# MagnetorquerFinalBoard.net
KiCad netlist of a schematic drawn in Altium Designer
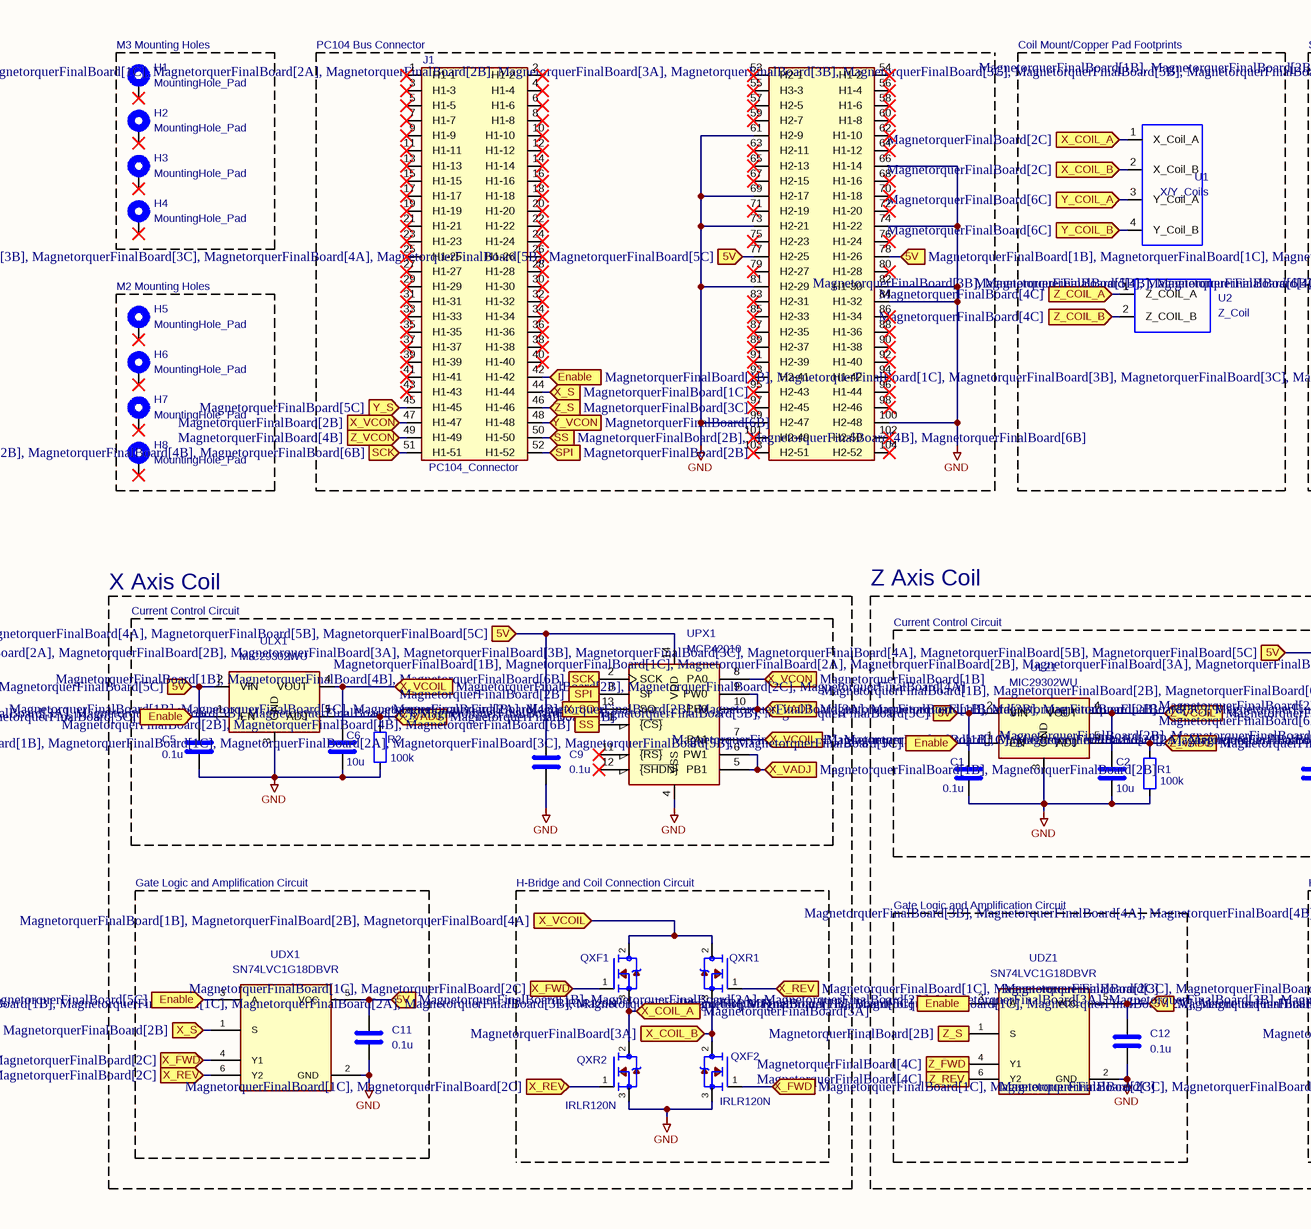
[diagram p0: MagnetorquerFinalBoard.SchDoc, left]
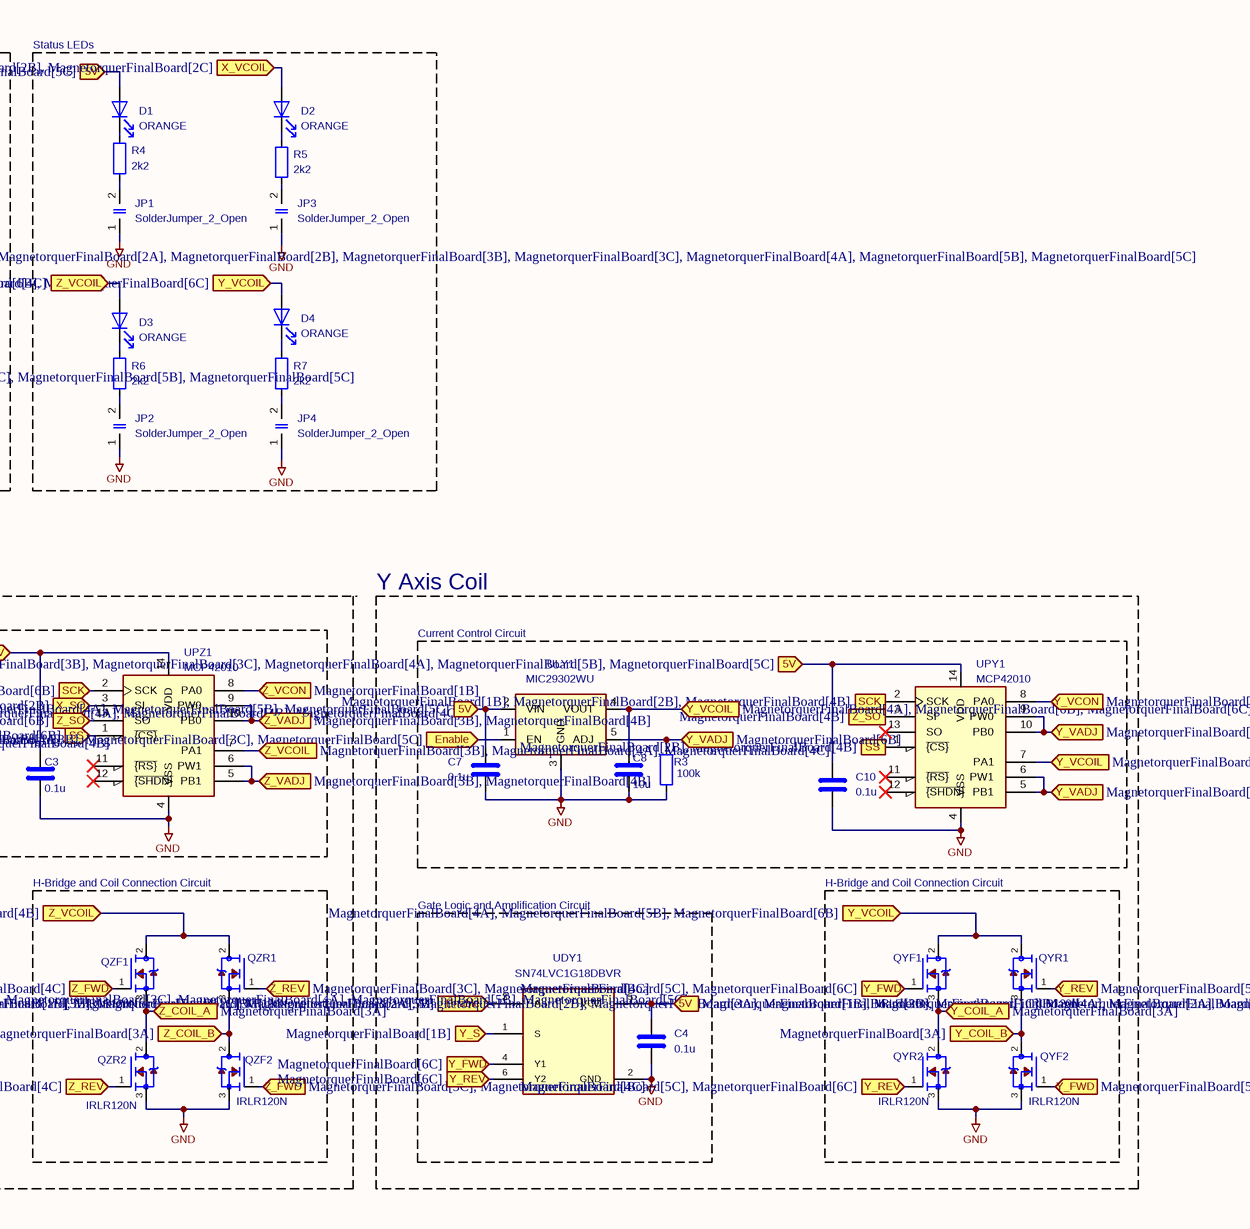
[diagram p1: MagnetorquerFinalBoard.SchDoc, right]

(export (version "E")
  (design (tool "Eeschema 10.0.6"))
  (components
    (comp (ref "C1") (value "0.1u") (footprint "C_0603_1608Metric") (libsource (lib "Device") (part "C")))
    (comp (ref "C2") (value "10u") (footprint "C_0603_1608Metric") (libsource (lib "Device") (part "C")))
    (comp (ref "C3") (value "0.1u") (footprint "C_0603_1608Metric") (libsource (lib "Device") (part "C")))
    (comp (ref "C4") (value "0.1u") (footprint "C_0603_1608Metric") (libsource (lib "Device") (part "C")))
    (comp (ref "C5") (value "0.1u") (footprint "C_0603_1608Metric") (libsource (lib "Device") (part "C")))
    (comp (ref "C6") (value "10u") (footprint "C_0603_1608Metric") (libsource (lib "Device") (part "C")))
    (comp (ref "C7") (value "0.1u") (footprint "C_0603_1608Metric") (libsource (lib "Device") (part "C")))
    (comp (ref "C8") (value "10u") (footprint "C_0603_1608Metric") (libsource (lib "Device") (part "C")))
    (comp (ref "C9") (value "0.1u") (footprint "C_0603_1608Metric") (libsource (lib "Device") (part "C")))
    (comp (ref "C10") (value "0.1u") (footprint "C_0603_1608Metric") (libsource (lib "Device") (part "C")))
    (comp (ref "C11") (value "0.1u") (footprint "C_0603_1608Metric") (libsource (lib "Device") (part "C")))
    (comp (ref "C12") (value "0.1u") (footprint "C_0603_1608Metric") (libsource (lib "Device") (part "C")))
    (comp (ref "D1")
      (value "ORANGE")
      (footprint "LED_0603_1608Metric")
      (libsource (lib "Device") (part "LED"))
    )
    (comp (ref "D2")
      (value "ORANGE")
      (footprint "LED_0603_1608Metric")
      (libsource (lib "Device") (part "LED"))
    )
    (comp (ref "D3")
      (value "ORANGE")
      (footprint "LED_0603_1608Metric")
      (libsource (lib "Device") (part "LED"))
    )
    (comp (ref "D4")
      (value "ORANGE")
      (footprint "LED_0603_1608Metric")
      (libsource (lib "Device") (part "LED"))
    )
    (comp (ref "H1")
      (value "MountingHole_Pad")
      (footprint "MountingHole_3.2mm_M3_Pad_TopBottom")
      (libsource (lib "Mechanical") (part "MountingHole_Pad"))
    )
    (comp (ref "H2")
      (value "MountingHole_Pad")
      (footprint "MountingHole_3.2mm_M3_Pad_TopBottom")
      (libsource (lib "Mechanical") (part "MountingHole_Pad"))
    )
    (comp (ref "H3")
      (value "MountingHole_Pad")
      (footprint "MountingHole_3.2mm_M3_Pad_TopBottom")
      (libsource (lib "Mechanical") (part "MountingHole_Pad"))
    )
    (comp (ref "H4")
      (value "MountingHole_Pad")
      (footprint "MountingHole_3.2mm_M3_Pad_TopBottom")
      (libsource (lib "Mechanical") (part "MountingHole_Pad"))
    )
    (comp (ref "H5")
      (value "MountingHole_Pad")
      (footprint "MountingHole_2.2mm_M2_Pad_TopBottom")
      (libsource (lib "Mechanical") (part "MountingHole_Pad"))
    )
    (comp (ref "H6")
      (value "MountingHole_Pad")
      (footprint "MountingHole_2.2mm_M2_Pad_TopBottom")
      (libsource (lib "Mechanical") (part "MountingHole_Pad"))
    )
    (comp (ref "H7")
      (value "MountingHole_Pad")
      (footprint "MountingHole_2.2mm_M2_Pad_TopBottom")
      (libsource (lib "Mechanical") (part "MountingHole_Pad"))
    )
    (comp (ref "H8")
      (value "MountingHole_Pad")
      (footprint "MountingHole_2.2mm_M2_Pad_TopBottom")
      (libsource (lib "Mechanical") (part "MountingHole_Pad"))
    )
    (comp (ref "J1")
      (value "PC104_Connector")
      (footprint "pc104-connector")
      (libsource (lib "qset-connector-library") (part "PC104_Connector"))
    )
    (comp (ref "JP1")
      (value "SolderJumper_2_Open")
      (footprint "SolderJumper-2_P1.3mm_Open_TrianglePad1.0x1.5mm")
      (libsource (lib "Jumper") (part "SolderJumper_2_Open"))
    )
    (comp (ref "JP2")
      (value "SolderJumper_2_Open")
      (footprint "SolderJumper-2_P1.3mm_Open_TrianglePad1.0x1.5mm")
      (libsource (lib "Jumper") (part "SolderJumper_2_Open"))
    )
    (comp (ref "JP3")
      (value "SolderJumper_2_Open")
      (footprint "SolderJumper-2_P1.3mm_Open_TrianglePad1.0x1.5mm")
      (libsource (lib "Jumper") (part "SolderJumper_2_Open"))
    )
    (comp (ref "JP4")
      (value "SolderJumper_2_Open")
      (footprint "SolderJumper-2_P1.3mm_Open_TrianglePad1.0x1.5mm")
      (libsource (lib "Jumper") (part "SolderJumper_2_Open"))
    )
    (comp (ref "QXF1")
      (value "IRLR120N")
      (footprint "TO-252-2")
      (fields (field (name "MANUFACTURER") "Infineon Technologies"))
      (libsource (lib "IRLR120N") (part "IRLR120N"))
    )
    (comp (ref "QXF2")
      (value "IRLR120N")
      (footprint "TO-252-2")
      (fields (field (name "MANUFACTURER") "Infineon Technologies"))
      (libsource (lib "IRLR120N") (part "IRLR120N"))
    )
    (comp (ref "QXR1")
      (value "IRLR120N")
      (footprint "TO-252-2")
      (fields (field (name "MANUFACTURER") "Infineon Technologies"))
      (libsource (lib "IRLR120N") (part "IRLR120N"))
    )
    (comp (ref "QXR2")
      (value "IRLR120N")
      (footprint "TO-252-2")
      (fields (field (name "MANUFACTURER") "Infineon Technologies"))
      (libsource (lib "IRLR120N") (part "IRLR120N"))
    )
    (comp (ref "QYF1")
      (value "IRLR120N")
      (footprint "TO-252-2")
      (fields (field (name "MANUFACTURER") "Infineon Technologies"))
      (libsource (lib "IRLR120N") (part "IRLR120N"))
    )
    (comp (ref "QYF2")
      (value "IRLR120N")
      (footprint "TO-252-2")
      (fields (field (name "MANUFACTURER") "Infineon Technologies"))
      (libsource (lib "IRLR120N") (part "IRLR120N"))
    )
    (comp (ref "QYR1")
      (value "IRLR120N")
      (footprint "TO-252-2")
      (fields (field (name "MANUFACTURER") "Infineon Technologies"))
      (libsource (lib "IRLR120N") (part "IRLR120N"))
    )
    (comp (ref "QYR2")
      (value "IRLR120N")
      (footprint "TO-252-2")
      (fields (field (name "MANUFACTURER") "Infineon Technologies"))
      (libsource (lib "IRLR120N") (part "IRLR120N"))
    )
    (comp (ref "QZF1")
      (value "IRLR120N")
      (footprint "TO-252-2")
      (fields (field (name "MANUFACTURER") "Infineon Technologies"))
      (libsource (lib "IRLR120N") (part "IRLR120N"))
    )
    (comp (ref "QZF2")
      (value "IRLR120N")
      (footprint "TO-252-2")
      (fields (field (name "MANUFACTURER") "Infineon Technologies"))
      (libsource (lib "IRLR120N") (part "IRLR120N"))
    )
    (comp (ref "QZR1")
      (value "IRLR120N")
      (footprint "TO-252-2")
      (fields (field (name "MANUFACTURER") "Infineon Technologies"))
      (libsource (lib "IRLR120N") (part "IRLR120N"))
    )
    (comp (ref "QZR2")
      (value "IRLR120N")
      (footprint "TO-252-2")
      (fields (field (name "MANUFACTURER") "Infineon Technologies"))
      (libsource (lib "IRLR120N") (part "IRLR120N"))
    )
    (comp (ref "R1") (value "100k") (footprint "R_0603_1608Metric") (libsource (lib "Device") (part "R")))
    (comp (ref "R2") (value "100k") (footprint "R_0603_1608Metric") (libsource (lib "Device") (part "R")))
    (comp (ref "R3") (value "100k") (footprint "R_0603_1608Metric") (libsource (lib "Device") (part "R")))
    (comp (ref "R4") (value "2k2") (footprint "R_0603_1608Metric") (libsource (lib "") (part "R_1")))
    (comp (ref "R5") (value "2k2") (footprint "R_0603_1608Metric") (libsource (lib "") (part "R_1")))
    (comp (ref "R6") (value "2k2") (footprint "R_0603_1608Metric") (libsource (lib "") (part "R_1")))
    (comp (ref "R7") (value "2k2") (footprint "R_0603_1608Metric") (libsource (lib "") (part "R_1")))
    (comp (ref "U1")
      (value "X/Y_Coils")
      (footprint "Front Coils Mount")
      (libsource (lib "Coils") (part "X/Y_Coils"))
    )
    (comp (ref "U2") (value "Z_Coil") (footprint "ZCoil") (libsource (lib "Coils") (part "Z_Coil")))
    (comp (ref "UDX1")
      (value "SN74LVC1G18DBVR")
      (footprint "SOT95P280X145-6N")
      (libsource (lib "SN74LVC1G18DBVR") (part "SN74LVC1G18DBVR"))
    )
    (comp (ref "UDY1")
      (value "SN74LVC1G18DBVR")
      (footprint "SOT95P280X145-6N")
      (libsource (lib "SN74LVC1G18DBVR") (part "SN74LVC1G18DBVR"))
    )
    (comp (ref "UDZ1")
      (value "SN74LVC1G18DBVR")
      (footprint "SOT95P280X145-6N")
      (libsource (lib "SN74LVC1G18DBVR") (part "SN74LVC1G18DBVR"))
    )
    (comp (ref "ULX1")
      (value "MIC29302WU")
      (footprint "TO-263-5_TabPin3")
      (libsource (lib "Regulator_Linear") (part "MIC29302WU"))
    )
    (comp (ref "ULY1")
      (value "MIC29302WU")
      (footprint "TO-263-5_TabPin3")
      (libsource (lib "Regulator_Linear") (part "MIC29302WU"))
    )
    (comp (ref "ULZ1")
      (value "MIC29302WU")
      (footprint "TO-263-5_TabPin3")
      (libsource (lib "Regulator_Linear") (part "MIC29302WU"))
    )
    (comp (ref "UPX1")
      (value "MCP42010")
      (footprint "SOIC127P600X175-14N")
      (libsource (lib "Potentiometer_Digital") (part "MCP42010"))
    )
    (comp (ref "UPY1")
      (value "MCP42010")
      (footprint "SOIC127P600X175-14N")
      (libsource (lib "Potentiometer_Digital") (part "MCP42010"))
    )
    (comp (ref "UPZ1")
      (value "MCP42010")
      (footprint "SOIC127P600X175-14N")
      (libsource (lib "Potentiometer_Digital") (part "MCP42010"))
    )
  )
  (nets
    (net (code "1") (name "/5V") (class "Default")
      (node (ref "C1") (pin "1") (pinfunction "1_1") (pintype "passive"))
      (node (ref "C10") (pin "1") (pinfunction "1_1") (pintype "passive"))
      (node (ref "C11") (pin "1") (pinfunction "1_1") (pintype "passive"))
      (node (ref "C12") (pin "1") (pinfunction "1_1") (pintype "passive"))
      (node (ref "C3") (pin "1") (pinfunction "1_1") (pintype "passive"))
      (node (ref "C4") (pin "1") (pinfunction "1_1") (pintype "passive"))
      (node (ref "C5") (pin "1") (pinfunction "1_1") (pintype "passive"))
      (node (ref "C7") (pin "1") (pinfunction "1_1") (pintype "passive"))
      (node (ref "C9") (pin "1") (pinfunction "1_1") (pintype "passive"))
      (node (ref "D1") (pin "2") (pinfunction "A_2") (pintype "passive"))
      (node (ref "J1") (pin "77") (pinfunction "H2-25_77") (pintype "passive"))
      (node (ref "J1") (pin "78") (pinfunction "H1-26_78") (pintype "passive"))
      (node (ref "UDX1") (pin "5") (pinfunction "VCC_5") (pintype "passive"))
      (node (ref "UDY1") (pin "5") (pinfunction "VCC_5") (pintype "passive"))
      (node (ref "UDZ1") (pin "5") (pinfunction "VCC_5") (pintype "passive"))
      (node (ref "ULX1") (pin "2") (pinfunction "VIN_2") (pintype "passive"))
      (node (ref "ULY1") (pin "2") (pinfunction "VIN_2") (pintype "passive"))
      (node (ref "ULZ1") (pin "2") (pinfunction "VIN_2") (pintype "passive"))
      (node (ref "UPX1") (pin "14") (pinfunction "VDD_14") (pintype "passive"))
      (node (ref "UPY1") (pin "14") (pinfunction "VDD_14") (pintype "passive"))
      (node (ref "UPZ1") (pin "14") (pinfunction "VDD_14") (pintype "passive"))
    )
    (net (code "2") (name "/Enable") (class "Default")
      (node (ref "J1") (pin "42") (pinfunction "H1-42_42") (pintype "passive"))
      (node (ref "UDX1") (pin "3") (pinfunction "A_3") (pintype "passive"))
      (node (ref "UDY1") (pin "3") (pinfunction "A_3") (pintype "passive"))
      (node (ref "UDZ1") (pin "3") (pinfunction "A_3") (pintype "passive"))
      (node (ref "ULX1") (pin "1") (pinfunction "EN_1") (pintype "passive"))
      (node (ref "ULY1") (pin "1") (pinfunction "EN_1") (pintype "passive"))
      (node (ref "ULZ1") (pin "1") (pinfunction "EN_1") (pintype "passive"))
    )
    (net (code "3") (name "/SCK") (class "Default")
      (node (ref "J1") (pin "51") (pinfunction "H1-51_51") (pintype "passive"))
      (node (ref "UPX1") (pin "2") (pinfunction "SCK_2") (pintype "passive"))
      (node (ref "UPY1") (pin "2") (pinfunction "SCK_2") (pintype "passive"))
      (node (ref "UPZ1") (pin "2") (pinfunction "SCK_2") (pintype "passive"))
    )
    (net (code "4") (name "/SPI") (class "Default")
      (node (ref "J1") (pin "52") (pinfunction "H1-52_52") (pintype "passive"))
      (node (ref "UPX1") (pin "3") (pinfunction "SI_3") (pintype "passive"))
    )
    (net (code "5") (name "/SS") (class "Default")
      (node (ref "J1") (pin "50") (pinfunction "H1-50_50") (pintype "passive"))
      (node (ref "UPX1") (pin "1") (pinfunction "~{{CS}}_1") (pintype "passive"))
      (node (ref "UPY1") (pin "1") (pinfunction "~{{CS}}_1") (pintype "passive"))
      (node (ref "UPZ1") (pin "1") (pinfunction "~{{CS}}_1") (pintype "passive"))
    )
    (net (code "6") (name "/X_COIL_A") (class "Default")
      (node (ref "QXF1") (pin "3") (pinfunction "3_3") (pintype "passive"))
      (node (ref "QXR2") (pin "2") (pinfunction "2_2") (pintype "passive"))
      (node (ref "U1") (pin "1") (pinfunction "X_Coil_A_1") (pintype "passive"))
    )
    (net (code "7") (name "/X_COIL_B") (class "Default")
      (node (ref "QXF2") (pin "2") (pinfunction "2_2") (pintype "passive"))
      (node (ref "QXR1") (pin "3") (pinfunction "3_3") (pintype "passive"))
      (node (ref "U1") (pin "2") (pinfunction "X_Coil_B_2") (pintype "passive"))
    )
    (net (code "8") (name "/X_FWD") (class "Default")
      (node (ref "QXF1") (pin "1") (pinfunction "1_1") (pintype "passive"))
      (node (ref "QXF2") (pin "1") (pinfunction "1_1") (pintype "passive"))
      (node (ref "UDX1") (pin "4") (pinfunction "Y1_4") (pintype "passive"))
    )
    (net (code "9") (name "/X_REV") (class "Default")
      (node (ref "QXR1") (pin "1") (pinfunction "1_1") (pintype "passive"))
      (node (ref "QXR2") (pin "1") (pinfunction "1_1") (pintype "passive"))
      (node (ref "UDX1") (pin "6") (pinfunction "Y2_6") (pintype "passive"))
    )
    (net (code "10") (name "/X_S") (class "Default")
      (node (ref "J1") (pin "44") (pinfunction "H1-44_44") (pintype "passive"))
      (node (ref "UDX1") (pin "1") (pinfunction "S_1") (pintype "passive"))
    )
    (net (code "11") (name "/X_SO") (class "Default")
      (node (ref "UPX1") (pin "13") (pinfunction "SO_13") (pintype "passive"))
      (node (ref "UPZ1") (pin "3") (pinfunction "SI_3") (pintype "passive"))
    )
    (net (code "12") (name "/X_VADJ") (class "Default")
      (node (ref "R2") (pin "2") (pinfunction "2_2") (pintype "passive"))
      (node (ref "ULX1") (pin "5") (pinfunction "ADJ_5") (pintype "passive"))
      (node (ref "UPX1") (pin "10") (pinfunction "PB0_10") (pintype "passive"))
      (node (ref "UPX1") (pin "5") (pinfunction "PB1_5") (pintype "passive"))
      (node (ref "UPX1") (pin "6") (pinfunction "PW1_6") (pintype "passive"))
      (node (ref "UPX1") (pin "9") (pinfunction "PW0_9") (pintype "passive"))
    )
    (net (code "13") (name "/X_VCOIL") (class "Default")
      (node (ref "C6") (pin "1") (pinfunction "1_1") (pintype "passive"))
      (node (ref "D2") (pin "2") (pinfunction "A_2") (pintype "passive"))
      (node (ref "QXF1") (pin "2") (pinfunction "2_2") (pintype "passive"))
      (node (ref "QXR1") (pin "2") (pinfunction "2_2") (pintype "passive"))
      (node (ref "ULX1") (pin "4") (pinfunction "VOUT_4") (pintype "passive"))
      (node (ref "UPX1") (pin "7") (pinfunction "PA1_7") (pintype "passive"))
    )
    (net (code "14") (name "/X_VCON") (class "Default")
      (node (ref "J1") (pin "47") (pinfunction "H1-47_47") (pintype "passive"))
      (node (ref "UPX1") (pin "8") (pinfunction "PA0_8") (pintype "passive"))
    )
    (net (code "15") (name "/Y_COIL_A") (class "Default")
      (node (ref "QYF1") (pin "3") (pinfunction "3_3") (pintype "passive"))
      (node (ref "QYR2") (pin "2") (pinfunction "2_2") (pintype "passive"))
      (node (ref "U1") (pin "3") (pinfunction "Y_Coil_A_3") (pintype "passive"))
    )
    (net (code "16") (name "/Y_COIL_B") (class "Default")
      (node (ref "QYF2") (pin "2") (pinfunction "2_2") (pintype "passive"))
      (node (ref "QYR1") (pin "3") (pinfunction "3_3") (pintype "passive"))
      (node (ref "U1") (pin "4") (pinfunction "Y_Coil_B_4") (pintype "passive"))
    )
    (net (code "17") (name "/Y_FWD") (class "Default")
      (node (ref "QYF1") (pin "1") (pinfunction "1_1") (pintype "passive"))
      (node (ref "QYF2") (pin "1") (pinfunction "1_1") (pintype "passive"))
      (node (ref "UDY1") (pin "4") (pinfunction "Y1_4") (pintype "passive"))
    )
    (net (code "18") (name "/Y_REV") (class "Default")
      (node (ref "QYR1") (pin "1") (pinfunction "1_1") (pintype "passive"))
      (node (ref "QYR2") (pin "1") (pinfunction "1_1") (pintype "passive"))
      (node (ref "UDY1") (pin "6") (pinfunction "Y2_6") (pintype "passive"))
    )
    (net (code "19") (name "/Y_S") (class "Default")
      (node (ref "J1") (pin "45") (pinfunction "H1-45_45") (pintype "passive"))
      (node (ref "UDY1") (pin "1") (pinfunction "S_1") (pintype "passive"))
    )
    (net (code "20") (name "/Y_VADJ") (class "Default")
      (node (ref "R3") (pin "2") (pinfunction "2_2") (pintype "passive"))
      (node (ref "ULY1") (pin "5") (pinfunction "ADJ_5") (pintype "passive"))
      (node (ref "UPY1") (pin "10") (pinfunction "PB0_10") (pintype "passive"))
      (node (ref "UPY1") (pin "5") (pinfunction "PB1_5") (pintype "passive"))
      (node (ref "UPY1") (pin "6") (pinfunction "PW1_6") (pintype "passive"))
      (node (ref "UPY1") (pin "9") (pinfunction "PW0_9") (pintype "passive"))
    )
    (net (code "21") (name "/Y_VCOIL") (class "Default")
      (node (ref "C8") (pin "1") (pinfunction "1_1") (pintype "passive"))
      (node (ref "D4") (pin "2") (pinfunction "A_2") (pintype "passive"))
      (node (ref "QYF1") (pin "2") (pinfunction "2_2") (pintype "passive"))
      (node (ref "QYR1") (pin "2") (pinfunction "2_2") (pintype "passive"))
      (node (ref "ULY1") (pin "4") (pinfunction "VOUT_4") (pintype "passive"))
      (node (ref "UPY1") (pin "7") (pinfunction "PA1_7") (pintype "passive"))
    )
    (net (code "22") (name "/Y_VCON") (class "Default")
      (node (ref "J1") (pin "48") (pinfunction "H1-48_48") (pintype "passive"))
      (node (ref "UPY1") (pin "8") (pinfunction "PA0_8") (pintype "passive"))
    )
    (net (code "23") (name "/Z_COIL_A") (class "Default")
      (node (ref "QZF1") (pin "3") (pinfunction "3_3") (pintype "passive"))
      (node (ref "QZR2") (pin "2") (pinfunction "2_2") (pintype "passive"))
      (node (ref "U2") (pin "1") (pinfunction "Z_COIL_A_1") (pintype "passive"))
    )
    (net (code "24") (name "/Z_COIL_B") (class "Default")
      (node (ref "QZF2") (pin "2") (pinfunction "2_2") (pintype "passive"))
      (node (ref "QZR1") (pin "3") (pinfunction "3_3") (pintype "passive"))
      (node (ref "U2") (pin "2") (pinfunction "Z_COIL_B_2") (pintype "passive"))
    )
    (net (code "25") (name "/Z_FWD") (class "Default")
      (node (ref "QZF1") (pin "1") (pinfunction "1_1") (pintype "passive"))
      (node (ref "QZF2") (pin "1") (pinfunction "1_1") (pintype "passive"))
      (node (ref "UDZ1") (pin "4") (pinfunction "Y1_4") (pintype "passive"))
    )
    (net (code "26") (name "/Z_REV") (class "Default")
      (node (ref "QZR1") (pin "1") (pinfunction "1_1") (pintype "passive"))
      (node (ref "QZR2") (pin "1") (pinfunction "1_1") (pintype "passive"))
      (node (ref "UDZ1") (pin "6") (pinfunction "Y2_6") (pintype "passive"))
    )
    (net (code "27") (name "/Z_S") (class "Default")
      (node (ref "J1") (pin "46") (pinfunction "H1-46_46") (pintype "passive"))
      (node (ref "UDZ1") (pin "1") (pinfunction "S_1") (pintype "passive"))
    )
    (net (code "28") (name "/Z_SO") (class "Default")
      (node (ref "UPY1") (pin "3") (pinfunction "SI_3") (pintype "passive"))
      (node (ref "UPZ1") (pin "13") (pinfunction "SO_13") (pintype "passive"))
    )
    (net (code "29") (name "/Z_VADJ") (class "Default")
      (node (ref "R1") (pin "2") (pinfunction "2_2") (pintype "passive"))
      (node (ref "ULZ1") (pin "5") (pinfunction "ADJ_5") (pintype "passive"))
      (node (ref "UPZ1") (pin "10") (pinfunction "PB0_10") (pintype "passive"))
      (node (ref "UPZ1") (pin "5") (pinfunction "PB1_5") (pintype "passive"))
      (node (ref "UPZ1") (pin "6") (pinfunction "PW1_6") (pintype "passive"))
      (node (ref "UPZ1") (pin "9") (pinfunction "PW0_9") (pintype "passive"))
    )
    (net (code "30") (name "/Z_VCOIL") (class "Default")
      (node (ref "C2") (pin "1") (pinfunction "1_1") (pintype "passive"))
      (node (ref "D3") (pin "2") (pinfunction "A_2") (pintype "passive"))
      (node (ref "QZF1") (pin "2") (pinfunction "2_2") (pintype "passive"))
      (node (ref "QZR1") (pin "2") (pinfunction "2_2") (pintype "passive"))
      (node (ref "ULZ1") (pin "4") (pinfunction "VOUT_4") (pintype "passive"))
      (node (ref "UPZ1") (pin "7") (pinfunction "PA1_7") (pintype "passive"))
    )
    (net (code "31") (name "/Z_VCON") (class "Default")
      (node (ref "J1") (pin "49") (pinfunction "H1-49_49") (pintype "passive"))
      (node (ref "UPZ1") (pin "8") (pinfunction "PA0_8") (pintype "passive"))
    )
    (net (code "32") (name "GND") (class "Default")
      (node (ref "C1") (pin "2") (pinfunction "2_2") (pintype "passive"))
      (node (ref "C10") (pin "2") (pinfunction "2_2") (pintype "passive"))
      (node (ref "C11") (pin "2") (pinfunction "2_2") (pintype "passive"))
      (node (ref "C12") (pin "2") (pinfunction "2_2") (pintype "passive"))
      (node (ref "C2") (pin "2") (pinfunction "2_2") (pintype "passive"))
      (node (ref "C3") (pin "2") (pinfunction "2_2") (pintype "passive"))
      (node (ref "C4") (pin "2") (pinfunction "2_2") (pintype "passive"))
      (node (ref "C5") (pin "2") (pinfunction "2_2") (pintype "passive"))
      (node (ref "C6") (pin "2") (pinfunction "2_2") (pintype "passive"))
      (node (ref "C7") (pin "2") (pinfunction "2_2") (pintype "passive"))
      (node (ref "C8") (pin "2") (pinfunction "2_2") (pintype "passive"))
      (node (ref "C9") (pin "2") (pinfunction "2_2") (pintype "passive"))
      (node (ref "J1") (pin "100") (pinfunction "H2-48_100") (pintype "passive"))
      (node (ref "J1") (pin "61") (pinfunction "H2-9_61") (pintype "passive"))
      (node (ref "J1") (pin "66") (pinfunction "H1-14_66") (pintype "passive"))
      (node (ref "J1") (pin "69") (pinfunction "H2-17_69") (pintype "passive"))
      (node (ref "J1") (pin "73") (pinfunction "H2-21_73") (pintype "passive"))
      (node (ref "J1") (pin "74") (pinfunction "H1-22_74") (pintype "passive"))
      (node (ref "J1") (pin "81") (pinfunction "H2-29_81") (pintype "passive"))
      (node (ref "J1") (pin "82") (pinfunction "H1-30_82") (pintype "passive"))
      (node (ref "J1") (pin "84") (pinfunction "H1-32_84") (pintype "passive"))
      (node (ref "J1") (pin "99") (pinfunction "H2-47_99") (pintype "passive"))
      (node (ref "JP1") (pin "1") (pinfunction "A_1") (pintype "passive"))
      (node (ref "JP2") (pin "1") (pinfunction "A_1") (pintype "passive"))
      (node (ref "JP3") (pin "1") (pinfunction "A_1") (pintype "passive"))
      (node (ref "JP4") (pin "1") (pinfunction "A_1") (pintype "passive"))
      (node (ref "QXF2") (pin "3") (pinfunction "3_3") (pintype "passive"))
      (node (ref "QXR2") (pin "3") (pinfunction "3_3") (pintype "passive"))
      (node (ref "QYF2") (pin "3") (pinfunction "3_3") (pintype "passive"))
      (node (ref "QYR2") (pin "3") (pinfunction "3_3") (pintype "passive"))
      (node (ref "QZF2") (pin "3") (pinfunction "3_3") (pintype "passive"))
      (node (ref "QZR2") (pin "3") (pinfunction "3_3") (pintype "passive"))
      (node (ref "R1") (pin "1") (pinfunction "1_1") (pintype "passive"))
      (node (ref "R2") (pin "1") (pinfunction "1_1") (pintype "passive"))
      (node (ref "R3") (pin "1") (pinfunction "1_1") (pintype "passive"))
      (node (ref "UDX1") (pin "2") (pinfunction "GND_2") (pintype "passive"))
      (node (ref "UDY1") (pin "2") (pinfunction "GND_2") (pintype "passive"))
      (node (ref "UDZ1") (pin "2") (pinfunction "GND_2") (pintype "passive"))
      (node (ref "ULX1") (pin "3") (pinfunction "GND_3") (pintype "passive"))
      (node (ref "ULY1") (pin "3") (pinfunction "GND_3") (pintype "passive"))
      (node (ref "ULZ1") (pin "3") (pinfunction "GND_3") (pintype "passive"))
      (node (ref "UPX1") (pin "4") (pinfunction "VSS_4") (pintype "passive"))
      (node (ref "UPY1") (pin "4") (pinfunction "VSS_4") (pintype "passive"))
      (node (ref "UPZ1") (pin "4") (pinfunction "VSS_4") (pintype "passive"))
    )
    (net (code "33") (name "Net-(D1-K)") (class "Default")
      (node (ref "D1") (pin "1") (pinfunction "K_1") (pintype "passive"))
      (node (ref "R4") (pin "1") (pinfunction "1_1") (pintype "passive"))
    )
    (net (code "34") (name "Net-(D2-K)") (class "Default")
      (node (ref "D2") (pin "1") (pinfunction "K_1") (pintype "passive"))
      (node (ref "R5") (pin "1") (pinfunction "1_1") (pintype "passive"))
    )
    (net (code "35") (name "Net-(D3-K)") (class "Default")
      (node (ref "D3") (pin "1") (pinfunction "K_1") (pintype "passive"))
      (node (ref "R6") (pin "1") (pinfunction "1_1") (pintype "passive"))
    )
    (net (code "36") (name "Net-(D4-K)") (class "Default")
      (node (ref "D4") (pin "1") (pinfunction "K_1") (pintype "passive"))
      (node (ref "R7") (pin "1") (pinfunction "1_1") (pintype "passive"))
    )
    (net (code "37") (name "Net-(JP1-B)") (class "Default")
      (node (ref "JP1") (pin "2") (pinfunction "B_2") (pintype "passive"))
      (node (ref "R4") (pin "2") (pinfunction "2_2") (pintype "passive"))
    )
    (net (code "38") (name "Net-(JP2-B)") (class "Default")
      (node (ref "JP2") (pin "2") (pinfunction "B_2") (pintype "passive"))
      (node (ref "R6") (pin "2") (pinfunction "2_2") (pintype "passive"))
    )
    (net (code "39") (name "Net-(JP3-B)") (class "Default")
      (node (ref "JP3") (pin "2") (pinfunction "B_2") (pintype "passive"))
      (node (ref "R5") (pin "2") (pinfunction "2_2") (pintype "passive"))
    )
    (net (code "40") (name "Net-(JP4-B)") (class "Default")
      (node (ref "JP4") (pin "2") (pinfunction "B_2") (pintype "passive"))
      (node (ref "R7") (pin "2") (pinfunction "2_2") (pintype "passive"))
    )
    (net (code "41") (name "unconnected-(H1-Pad1)") (class "Default")
      (node (ref "H1") (pin "1") (pinfunction "1_1") (pintype "passive+no_connect"))
    )
    (net (code "42") (name "unconnected-(H2-Pad1)") (class "Default")
      (node (ref "H2") (pin "1") (pinfunction "1_1") (pintype "passive+no_connect"))
    )
    (net (code "43") (name "unconnected-(H3-Pad1)") (class "Default")
      (node (ref "H3") (pin "1") (pinfunction "1_1") (pintype "passive+no_connect"))
    )
    (net (code "44") (name "unconnected-(H4-Pad1)") (class "Default")
      (node (ref "H4") (pin "1") (pinfunction "1_1") (pintype "passive+no_connect"))
    )
    (net (code "45") (name "unconnected-(H5-Pad1)") (class "Default")
      (node (ref "H5") (pin "1") (pinfunction "1_1") (pintype "passive+no_connect"))
    )
    (net (code "46") (name "unconnected-(H6-Pad1)") (class "Default")
      (node (ref "H6") (pin "1") (pinfunction "1_1") (pintype "passive+no_connect"))
    )
    (net (code "47") (name "unconnected-(H7-Pad1)") (class "Default")
      (node (ref "H7") (pin "1") (pinfunction "1_1") (pintype "passive+no_connect"))
    )
    (net (code "48") (name "unconnected-(H8-Pad1)") (class "Default")
      (node (ref "H8") (pin "1") (pinfunction "1_1") (pintype "passive+no_connect"))
    )
    (net (code "49") (name "unconnected-(J1-H1-1-Pad1)") (class "Default")
      (node (ref "J1") (pin "1") (pinfunction "H1-1_1") (pintype "passive+no_connect"))
    )
    (net (code "50") (name "unconnected-(J1-H1-2-Pad2)") (class "Default")
      (node (ref "J1") (pin "2") (pinfunction "H1-2_2") (pintype "passive+no_connect"))
    )
    (net (code "51") (name "unconnected-(J1-H1-2-Pad54)") (class "Default")
      (node (ref "J1") (pin "54") (pinfunction "H1-2_54") (pintype "passive+no_connect"))
    )
    (net (code "52") (name "unconnected-(J1-H1-3-Pad3)") (class "Default")
      (node (ref "J1") (pin "3") (pinfunction "H1-3_3") (pintype "passive+no_connect"))
    )
    (net (code "53") (name "unconnected-(J1-H1-4-Pad4)") (class "Default")
      (node (ref "J1") (pin "4") (pinfunction "H1-4_4") (pintype "passive+no_connect"))
    )
    (net (code "54") (name "unconnected-(J1-H1-4-Pad56)") (class "Default")
      (node (ref "J1") (pin "56") (pinfunction "H1-4_56") (pintype "passive+no_connect"))
    )
    (net (code "55") (name "unconnected-(J1-H1-5-Pad5)") (class "Default")
      (node (ref "J1") (pin "5") (pinfunction "H1-5_5") (pintype "passive+no_connect"))
    )
    (net (code "56") (name "unconnected-(J1-H1-6-Pad6)") (class "Default")
      (node (ref "J1") (pin "6") (pinfunction "H1-6_6") (pintype "passive+no_connect"))
    )
    (net (code "57") (name "unconnected-(J1-H1-6-Pad58)") (class "Default")
      (node (ref "J1") (pin "58") (pinfunction "H1-6_58") (pintype "passive+no_connect"))
    )
    (net (code "58") (name "unconnected-(J1-H1-7-Pad7)") (class "Default")
      (node (ref "J1") (pin "7") (pinfunction "H1-7_7") (pintype "passive+no_connect"))
    )
    (net (code "59") (name "unconnected-(J1-H1-8-Pad8)") (class "Default")
      (node (ref "J1") (pin "8") (pinfunction "H1-8_8") (pintype "passive+no_connect"))
    )
    (net (code "60") (name "unconnected-(J1-H1-8-Pad60)") (class "Default")
      (node (ref "J1") (pin "60") (pinfunction "H1-8_60") (pintype "passive+no_connect"))
    )
    (net (code "61") (name "unconnected-(J1-H1-9-Pad9)") (class "Default")
      (node (ref "J1") (pin "9") (pinfunction "H1-9_9") (pintype "passive+no_connect"))
    )
    (net (code "62") (name "unconnected-(J1-H1-10-Pad10)") (class "Default")
      (node (ref "J1") (pin "10") (pinfunction "H1-10_10") (pintype "passive+no_connect"))
    )
    (net (code "63") (name "unconnected-(J1-H1-10-Pad62)") (class "Default")
      (node (ref "J1") (pin "62") (pinfunction "H1-10_62") (pintype "passive+no_connect"))
    )
    (net (code "64") (name "unconnected-(J1-H1-11-Pad11)") (class "Default")
      (node (ref "J1") (pin "11") (pinfunction "H1-11_11") (pintype "passive+no_connect"))
    )
    (net (code "65") (name "unconnected-(J1-H1-12-Pad12)") (class "Default")
      (node (ref "J1") (pin "12") (pinfunction "H1-12_12") (pintype "passive+no_connect"))
    )
    (net (code "66") (name "unconnected-(J1-H1-12-Pad64)") (class "Default")
      (node (ref "J1") (pin "64") (pinfunction "H1-12_64") (pintype "passive+no_connect"))
    )
    (net (code "67") (name "unconnected-(J1-H1-13-Pad13)") (class "Default")
      (node (ref "J1") (pin "13") (pinfunction "H1-13_13") (pintype "passive+no_connect"))
    )
    (net (code "68") (name "unconnected-(J1-H1-14-Pad14)") (class "Default")
      (node (ref "J1") (pin "14") (pinfunction "H1-14_14") (pintype "passive+no_connect"))
    )
    (net (code "69") (name "unconnected-(J1-H1-15-Pad15)") (class "Default")
      (node (ref "J1") (pin "15") (pinfunction "H1-15_15") (pintype "passive+no_connect"))
    )
    (net (code "70") (name "unconnected-(J1-H1-16-Pad16)") (class "Default")
      (node (ref "J1") (pin "16") (pinfunction "H1-16_16") (pintype "passive+no_connect"))
    )
    (net (code "71") (name "unconnected-(J1-H1-16-Pad68)") (class "Default")
      (node (ref "J1") (pin "68") (pinfunction "H1-16_68") (pintype "passive+no_connect"))
    )
    (net (code "72") (name "unconnected-(J1-H1-17-Pad17)") (class "Default")
      (node (ref "J1") (pin "17") (pinfunction "H1-17_17") (pintype "passive+no_connect"))
    )
    (net (code "73") (name "unconnected-(J1-H1-18-Pad18)") (class "Default")
      (node (ref "J1") (pin "18") (pinfunction "H1-18_18") (pintype "passive+no_connect"))
    )
    (net (code "74") (name "unconnected-(J1-H1-18-Pad70)") (class "Default")
      (node (ref "J1") (pin "70") (pinfunction "H1-18_70") (pintype "passive+no_connect"))
    )
    (net (code "75") (name "unconnected-(J1-H1-19-Pad19)") (class "Default")
      (node (ref "J1") (pin "19") (pinfunction "H1-19_19") (pintype "passive+no_connect"))
    )
    (net (code "76") (name "unconnected-(J1-H1-20-Pad20)") (class "Default")
      (node (ref "J1") (pin "20") (pinfunction "H1-20_20") (pintype "passive+no_connect"))
    )
    (net (code "77") (name "unconnected-(J1-H1-20-Pad72)") (class "Default")
      (node (ref "J1") (pin "72") (pinfunction "H1-20_72") (pintype "passive+no_connect"))
    )
    (net (code "78") (name "unconnected-(J1-H1-21-Pad21)") (class "Default")
      (node (ref "J1") (pin "21") (pinfunction "H1-21_21") (pintype "passive+no_connect"))
    )
    (net (code "79") (name "unconnected-(J1-H1-22-Pad22)") (class "Default")
      (node (ref "J1") (pin "22") (pinfunction "H1-22_22") (pintype "passive+no_connect"))
    )
    (net (code "80") (name "unconnected-(J1-H1-23-Pad23)") (class "Default")
      (node (ref "J1") (pin "23") (pinfunction "H1-23_23") (pintype "passive+no_connect"))
    )
    (net (code "81") (name "unconnected-(J1-H1-24-Pad24)") (class "Default")
      (node (ref "J1") (pin "24") (pinfunction "H1-24_24") (pintype "passive+no_connect"))
    )
    (net (code "82") (name "unconnected-(J1-H1-24-Pad76)") (class "Default")
      (node (ref "J1") (pin "76") (pinfunction "H1-24_76") (pintype "passive+no_connect"))
    )
    (net (code "83") (name "unconnected-(J1-H1-25-Pad25)") (class "Default")
      (node (ref "J1") (pin "25") (pinfunction "H1-25_25") (pintype "passive+no_connect"))
    )
    (net (code "84") (name "unconnected-(J1-H1-26-Pad26)") (class "Default")
      (node (ref "J1") (pin "26") (pinfunction "H1-26_26") (pintype "passive+no_connect"))
    )
    (net (code "85") (name "unconnected-(J1-H1-27-Pad27)") (class "Default")
      (node (ref "J1") (pin "27") (pinfunction "H1-27_27") (pintype "passive+no_connect"))
    )
    (net (code "86") (name "unconnected-(J1-H1-28-Pad28)") (class "Default")
      (node (ref "J1") (pin "28") (pinfunction "H1-28_28") (pintype "passive+no_connect"))
    )
    (net (code "87") (name "unconnected-(J1-H1-28-Pad80)") (class "Default")
      (node (ref "J1") (pin "80") (pinfunction "H1-28_80") (pintype "passive+no_connect"))
    )
    (net (code "88") (name "unconnected-(J1-H1-29-Pad29)") (class "Default")
      (node (ref "J1") (pin "29") (pinfunction "H1-29_29") (pintype "passive+no_connect"))
    )
    (net (code "89") (name "unconnected-(J1-H1-30-Pad30)") (class "Default")
      (node (ref "J1") (pin "30") (pinfunction "H1-30_30") (pintype "passive+no_connect"))
    )
    (net (code "90") (name "unconnected-(J1-H1-31-Pad31)") (class "Default")
      (node (ref "J1") (pin "31") (pinfunction "H1-31_31") (pintype "passive+no_connect"))
    )
    (net (code "91") (name "unconnected-(J1-H1-32-Pad32)") (class "Default")
      (node (ref "J1") (pin "32") (pinfunction "H1-32_32") (pintype "passive+no_connect"))
    )
    (net (code "92") (name "unconnected-(J1-H1-33-Pad33)") (class "Default")
      (node (ref "J1") (pin "33") (pinfunction "H1-33_33") (pintype "passive+no_connect"))
    )
    (net (code "93") (name "unconnected-(J1-H1-34-Pad34)") (class "Default")
      (node (ref "J1") (pin "34") (pinfunction "H1-34_34") (pintype "passive+no_connect"))
    )
    (net (code "94") (name "unconnected-(J1-H1-34-Pad86)") (class "Default")
      (node (ref "J1") (pin "86") (pinfunction "H1-34_86") (pintype "passive+no_connect"))
    )
    (net (code "95") (name "unconnected-(J1-H1-35-Pad35)") (class "Default")
      (node (ref "J1") (pin "35") (pinfunction "H1-35_35") (pintype "passive+no_connect"))
    )
    (net (code "96") (name "unconnected-(J1-H1-36-Pad36)") (class "Default")
      (node (ref "J1") (pin "36") (pinfunction "H1-36_36") (pintype "passive+no_connect"))
    )
    (net (code "97") (name "unconnected-(J1-H1-36-Pad88)") (class "Default")
      (node (ref "J1") (pin "88") (pinfunction "H1-36_88") (pintype "passive+no_connect"))
    )
    (net (code "98") (name "unconnected-(J1-H1-37-Pad37)") (class "Default")
      (node (ref "J1") (pin "37") (pinfunction "H1-37_37") (pintype "passive+no_connect"))
    )
    (net (code "99") (name "unconnected-(J1-H1-38-Pad38)") (class "Default")
      (node (ref "J1") (pin "38") (pinfunction "H1-38_38") (pintype "passive+no_connect"))
    )
    (net (code "100") (name "unconnected-(J1-H1-38-Pad90)") (class "Default")
      (node (ref "J1") (pin "90") (pinfunction "H1-38_90") (pintype "passive+no_connect"))
    )
    (net (code "101") (name "unconnected-(J1-H1-39-Pad39)") (class "Default")
      (node (ref "J1") (pin "39") (pinfunction "H1-39_39") (pintype "passive+no_connect"))
    )
    (net (code "102") (name "unconnected-(J1-H1-40-Pad40)") (class "Default")
      (node (ref "J1") (pin "40") (pinfunction "H1-40_40") (pintype "passive+no_connect"))
    )
    (net (code "103") (name "unconnected-(J1-H1-40-Pad92)") (class "Default")
      (node (ref "J1") (pin "92") (pinfunction "H1-40_92") (pintype "passive+no_connect"))
    )
    (net (code "104") (name "unconnected-(J1-H1-41-Pad41)") (class "Default")
      (node (ref "J1") (pin "41") (pinfunction "H1-41_41") (pintype "passive+no_connect"))
    )
    (net (code "105") (name "unconnected-(J1-H1-42-Pad94)") (class "Default")
      (node (ref "J1") (pin "94") (pinfunction "H1-42_94") (pintype "passive+no_connect"))
    )
    (net (code "106") (name "unconnected-(J1-H1-43-Pad43)") (class "Default")
      (node (ref "J1") (pin "43") (pinfunction "H1-43_43") (pintype "passive+no_connect"))
    )
    (net (code "107") (name "unconnected-(J1-H1-44-Pad96)") (class "Default")
      (node (ref "J1") (pin "96") (pinfunction "H1-44_96") (pintype "passive+no_connect"))
    )
    (net (code "108") (name "unconnected-(J1-H2-1-Pad53)") (class "Default")
      (node (ref "J1") (pin "53") (pinfunction "H2-1_53") (pintype "passive+no_connect"))
    )
    (net (code "109") (name "unconnected-(J1-H2-5-Pad57)") (class "Default")
      (node (ref "J1") (pin "57") (pinfunction "H2-5_57") (pintype "passive+no_connect"))
    )
    (net (code "110") (name "unconnected-(J1-H2-7-Pad59)") (class "Default")
      (node (ref "J1") (pin "59") (pinfunction "H2-7_59") (pintype "passive+no_connect"))
    )
    (net (code "111") (name "unconnected-(J1-H2-11-Pad63)") (class "Default")
      (node (ref "J1") (pin "63") (pinfunction "H2-11_63") (pintype "passive+no_connect"))
    )
    (net (code "112") (name "unconnected-(J1-H2-13-Pad65)") (class "Default")
      (node (ref "J1") (pin "65") (pinfunction "H2-13_65") (pintype "passive+no_connect"))
    )
    (net (code "113") (name "unconnected-(J1-H2-15-Pad67)") (class "Default")
      (node (ref "J1") (pin "67") (pinfunction "H2-15_67") (pintype "passive+no_connect"))
    )
    (net (code "114") (name "unconnected-(J1-H2-19-Pad71)") (class "Default")
      (node (ref "J1") (pin "71") (pinfunction "H2-19_71") (pintype "passive+no_connect"))
    )
    (net (code "115") (name "unconnected-(J1-H2-23-Pad75)") (class "Default")
      (node (ref "J1") (pin "75") (pinfunction "H2-23_75") (pintype "passive+no_connect"))
    )
    (net (code "116") (name "unconnected-(J1-H2-27-Pad79)") (class "Default")
      (node (ref "J1") (pin "79") (pinfunction "H2-27_79") (pintype "passive+no_connect"))
    )
    (net (code "117") (name "unconnected-(J1-H2-31-Pad83)") (class "Default")
      (node (ref "J1") (pin "83") (pinfunction "H2-31_83") (pintype "passive+no_connect"))
    )
    (net (code "118") (name "unconnected-(J1-H2-33-Pad85)") (class "Default")
      (node (ref "J1") (pin "85") (pinfunction "H2-33_85") (pintype "passive+no_connect"))
    )
    (net (code "119") (name "unconnected-(J1-H2-35-Pad87)") (class "Default")
      (node (ref "J1") (pin "87") (pinfunction "H2-35_87") (pintype "passive+no_connect"))
    )
    (net (code "120") (name "unconnected-(J1-H2-37-Pad89)") (class "Default")
      (node (ref "J1") (pin "89") (pinfunction "H2-37_89") (pintype "passive+no_connect"))
    )
    (net (code "121") (name "unconnected-(J1-H2-39-Pad91)") (class "Default")
      (node (ref "J1") (pin "91") (pinfunction "H2-39_91") (pintype "passive+no_connect"))
    )
    (net (code "122") (name "unconnected-(J1-H2-41-Pad93)") (class "Default")
      (node (ref "J1") (pin "93") (pinfunction "H2-41_93") (pintype "passive+no_connect"))
    )
    (net (code "123") (name "unconnected-(J1-H2-43-Pad95)") (class "Default")
      (node (ref "J1") (pin "95") (pinfunction "H2-43_95") (pintype "passive+no_connect"))
    )
    (net (code "124") (name "unconnected-(J1-H2-45-Pad97)") (class "Default")
      (node (ref "J1") (pin "97") (pinfunction "H2-45_97") (pintype "passive+no_connect"))
    )
    (net (code "125") (name "unconnected-(J1-H2-46-Pad98)") (class "Default")
      (node (ref "J1") (pin "98") (pinfunction "H2-46_98") (pintype "passive+no_connect"))
    )
    (net (code "126") (name "unconnected-(J1-H2-49-Pad101)") (class "Default")
      (node (ref "J1") (pin "101") (pinfunction "H2-49_101") (pintype "passive+no_connect"))
    )
    (net (code "127") (name "unconnected-(J1-H2-50-Pad102)") (class "Default")
      (node (ref "J1") (pin "102") (pinfunction "H2-50_102") (pintype "passive+no_connect"))
    )
    (net (code "128") (name "unconnected-(J1-H2-51-Pad103)") (class "Default")
      (node (ref "J1") (pin "103") (pinfunction "H2-51_103") (pintype "passive+no_connect"))
    )
    (net (code "129") (name "unconnected-(J1-H2-52-Pad104)") (class "Default")
      (node (ref "J1") (pin "104") (pinfunction "H2-52_104") (pintype "passive+no_connect"))
    )
    (net (code "130") (name "unconnected-(J1-H3-3-Pad55)") (class "Default")
      (node (ref "J1") (pin "55") (pinfunction "H3-3_55") (pintype "passive+no_connect"))
    )
    (net (code "131") (name "unconnected-(UPX1-~{{RS}}-Pad11)") (class "Default")
      (node (ref "UPX1") (pin "11") (pinfunction "~{{RS}}_11") (pintype "passive+no_connect"))
    )
    (net (code "132") (name "unconnected-(UPX1-~{{SHDN}}-Pad12)") (class "Default")
      (node (ref "UPX1") (pin "12") (pinfunction "~{{SHDN}}_12") (pintype "passive+no_connect"))
    )
    (net (code "133") (name "unconnected-(UPY1-SO-Pad13)") (class "Default")
      (node (ref "UPY1") (pin "13") (pinfunction "SO_13") (pintype "passive+no_connect"))
    )
    (net (code "134") (name "unconnected-(UPY1-~{{RS}}-Pad11)") (class "Default")
      (node (ref "UPY1") (pin "11") (pinfunction "~{{RS}}_11") (pintype "passive+no_connect"))
    )
    (net (code "135") (name "unconnected-(UPY1-~{{SHDN}}-Pad12)") (class "Default")
      (node (ref "UPY1") (pin "12") (pinfunction "~{{SHDN}}_12") (pintype "passive+no_connect"))
    )
    (net (code "136") (name "unconnected-(UPZ1-~{{RS}}-Pad11)") (class "Default")
      (node (ref "UPZ1") (pin "11") (pinfunction "~{{RS}}_11") (pintype "passive+no_connect"))
    )
    (net (code "137") (name "unconnected-(UPZ1-~{{SHDN}}-Pad12)") (class "Default")
      (node (ref "UPZ1") (pin "12") (pinfunction "~{{SHDN}}_12") (pintype "passive+no_connect"))
    )
  )
)
